# Sheet.net
KiCad netlist of a schematic drawn in Altium Designer
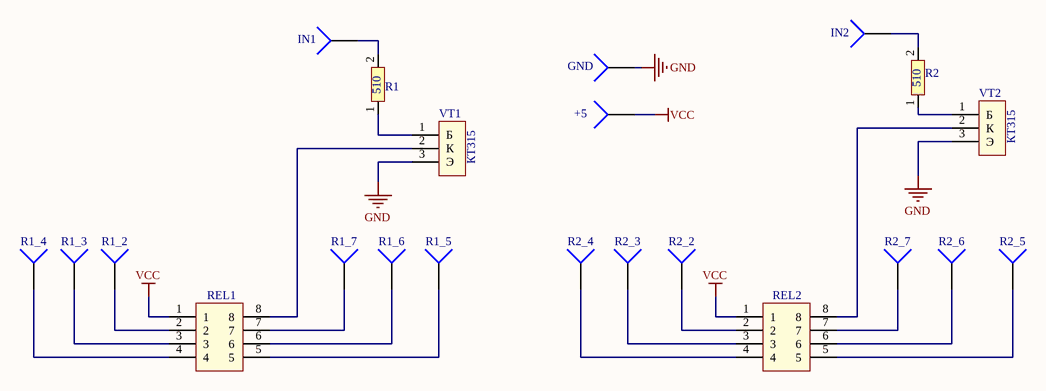
[diagram p0: Sheet.SchDoc]

(export (version "E")
  (design (tool "Eeschema 10.0.6"))
  (components
    (comp (ref "J1")
      (value "IN2")
      (footprint "PIN1")
      (description "Socket")
      (fields (field (name "PUBLISHER") "Altium Limited"))
      (libsource (lib "Miscellaneous Connectors") (part "Socket"))
    )
    (comp (ref "J2")
      (value "IN1")
      (footprint "PIN1")
      (description "Socket")
      (fields (field (name "PUBLISHER") "Altium Limited"))
      (libsource (lib "Miscellaneous Connectors") (part "Socket"))
    )
    (comp (ref "J3")
      (value "GND")
      (footprint "PIN1")
      (description "Socket")
      (fields (field (name "PUBLISHER") "Altium Limited"))
      (libsource (lib "Miscellaneous Connectors") (part "Socket"))
    )
    (comp (ref "J4")
      (value "+5")
      (footprint "PIN1")
      (description "Socket")
      (fields (field (name "PUBLISHER") "Altium Limited"))
      (libsource (lib "Miscellaneous Connectors") (part "Socket"))
    )
    (comp (ref "J5")
      (value "R1_4")
      (footprint "PIN1")
      (description "Socket")
      (fields (field (name "PUBLISHER") "Altium Limited"))
      (libsource (lib "Miscellaneous Connectors") (part "Socket"))
    )
    (comp (ref "J6")
      (value "R1_3")
      (footprint "PIN1")
      (description "Socket")
      (fields (field (name "PUBLISHER") "Altium Limited"))
      (libsource (lib "Miscellaneous Connectors") (part "Socket"))
    )
    (comp (ref "J7")
      (value "R1_2")
      (footprint "PIN1")
      (description "Socket")
      (fields (field (name "PUBLISHER") "Altium Limited"))
      (libsource (lib "Miscellaneous Connectors") (part "Socket"))
    )
    (comp (ref "J8")
      (value "R1_7")
      (footprint "PIN1")
      (description "Socket")
      (fields (field (name "PUBLISHER") "Altium Limited"))
      (libsource (lib "Miscellaneous Connectors") (part "Socket"))
    )
    (comp (ref "J9")
      (value "R1_6")
      (footprint "PIN1")
      (description "Socket")
      (fields (field (name "PUBLISHER") "Altium Limited"))
      (libsource (lib "Miscellaneous Connectors") (part "Socket"))
    )
    (comp (ref "J10")
      (value "R1_5")
      (footprint "PIN1")
      (description "Socket")
      (fields (field (name "PUBLISHER") "Altium Limited"))
      (libsource (lib "Miscellaneous Connectors") (part "Socket"))
    )
    (comp (ref "J11")
      (value "R2_4")
      (footprint "PIN1")
      (description "Socket")
      (fields (field (name "PUBLISHER") "Altium Limited"))
      (libsource (lib "Miscellaneous Connectors") (part "Socket"))
    )
    (comp (ref "J12")
      (value "R2_3")
      (footprint "PIN1")
      (description "Socket")
      (fields (field (name "PUBLISHER") "Altium Limited"))
      (libsource (lib "Miscellaneous Connectors") (part "Socket"))
    )
    (comp (ref "J13")
      (value "R2_2")
      (footprint "PIN1")
      (description "Socket")
      (fields (field (name "PUBLISHER") "Altium Limited"))
      (libsource (lib "Miscellaneous Connectors") (part "Socket"))
    )
    (comp (ref "J14")
      (value "R2_7")
      (footprint "PIN1")
      (description "Socket")
      (fields (field (name "PUBLISHER") "Altium Limited"))
      (libsource (lib "Miscellaneous Connectors") (part "Socket"))
    )
    (comp (ref "J15")
      (value "R2_6")
      (footprint "PIN1")
      (description "Socket")
      (fields (field (name "PUBLISHER") "Altium Limited"))
      (libsource (lib "Miscellaneous Connectors") (part "Socket"))
    )
    (comp (ref "J16")
      (value "R2_5")
      (footprint "PIN1")
      (description "Socket")
      (fields (field (name "PUBLISHER") "Altium Limited"))
      (libsource (lib "Miscellaneous Connectors") (part "Socket"))
    )
    (comp (ref "R1") (value "510") (footprint "RES") (libsource (lib "Schlib") (part "RES")))
    (comp (ref "R2") (value "510") (footprint "RES") (libsource (lib "Schlib") (part "RES")))
    (comp (ref "REL1") (value "IM03TS") (footprint "IM03TS") (libsource (lib "Schlib") (part "IM03TS")))
    (comp (ref "REL2") (value "IM03TS") (footprint "IM03TS") (libsource (lib "Schlib") (part "IM03TS")))
    (comp (ref "VT1") (value "КТ315") (footprint "KT315") (libsource (lib "Schlib") (part "КТ315")))
    (comp (ref "VT2") (value "КТ315") (footprint "KT315") (libsource (lib "Schlib") (part "КТ315")))
  )
  (nets
    (net (code "1") (name "GND") (class "Default")
      (node (ref "J3") (pin "1") (pinfunction "1_1") (pintype "passive"))
      (node (ref "VT1") (pin "3") (pinfunction "Э_3") (pintype "passive"))
      (node (ref "VT2") (pin "3") (pinfunction "Э_3") (pintype "passive"))
    )
    (net (code "2") (name "Net-(J1-Pad1)") (class "Default")
      (node (ref "J1") (pin "1") (pinfunction "1_1") (pintype "passive"))
      (node (ref "R2") (pin "2") (pinfunction "2_2") (pintype "passive"))
    )
    (net (code "3") (name "Net-(J2-Pad1)") (class "Default")
      (node (ref "J2") (pin "1") (pinfunction "1_1") (pintype "passive"))
      (node (ref "R1") (pin "2") (pinfunction "2_2") (pintype "passive"))
    )
    (net (code "4") (name "Net-(J5-Pad1)") (class "Default")
      (node (ref "J5") (pin "1") (pinfunction "1_1") (pintype "passive"))
      (node (ref "REL1") (pin "4") (pinfunction "4_4") (pintype "passive"))
    )
    (net (code "5") (name "Net-(J6-Pad1)") (class "Default")
      (node (ref "J6") (pin "1") (pinfunction "1_1") (pintype "passive"))
      (node (ref "REL1") (pin "3") (pinfunction "3_3") (pintype "passive"))
    )
    (net (code "6") (name "Net-(J7-Pad1)") (class "Default")
      (node (ref "J7") (pin "1") (pinfunction "1_1") (pintype "passive"))
      (node (ref "REL1") (pin "2") (pinfunction "2_2") (pintype "passive"))
    )
    (net (code "7") (name "Net-(J8-Pad1)") (class "Default")
      (node (ref "J8") (pin "1") (pinfunction "1_1") (pintype "passive"))
      (node (ref "REL1") (pin "7") (pinfunction "7_7") (pintype "passive"))
    )
    (net (code "8") (name "Net-(J9-Pad1)") (class "Default")
      (node (ref "J9") (pin "1") (pinfunction "1_1") (pintype "passive"))
      (node (ref "REL1") (pin "6") (pinfunction "6_6") (pintype "passive"))
    )
    (net (code "9") (name "Net-(J10-Pad1)") (class "Default")
      (node (ref "J10") (pin "1") (pinfunction "1_1") (pintype "passive"))
      (node (ref "REL1") (pin "5") (pinfunction "5_5") (pintype "passive"))
    )
    (net (code "10") (name "Net-(J11-Pad1)") (class "Default")
      (node (ref "J11") (pin "1") (pinfunction "1_1") (pintype "passive"))
      (node (ref "REL2") (pin "4") (pinfunction "4_4") (pintype "passive"))
    )
    (net (code "11") (name "Net-(J12-Pad1)") (class "Default")
      (node (ref "J12") (pin "1") (pinfunction "1_1") (pintype "passive"))
      (node (ref "REL2") (pin "3") (pinfunction "3_3") (pintype "passive"))
    )
    (net (code "12") (name "Net-(J13-Pad1)") (class "Default")
      (node (ref "J13") (pin "1") (pinfunction "1_1") (pintype "passive"))
      (node (ref "REL2") (pin "2") (pinfunction "2_2") (pintype "passive"))
    )
    (net (code "13") (name "Net-(J14-Pad1)") (class "Default")
      (node (ref "J14") (pin "1") (pinfunction "1_1") (pintype "passive"))
      (node (ref "REL2") (pin "7") (pinfunction "7_7") (pintype "passive"))
    )
    (net (code "14") (name "Net-(J15-Pad1)") (class "Default")
      (node (ref "J15") (pin "1") (pinfunction "1_1") (pintype "passive"))
      (node (ref "REL2") (pin "6") (pinfunction "6_6") (pintype "passive"))
    )
    (net (code "15") (name "Net-(J16-Pad1)") (class "Default")
      (node (ref "J16") (pin "1") (pinfunction "1_1") (pintype "passive"))
      (node (ref "REL2") (pin "5") (pinfunction "5_5") (pintype "passive"))
    )
    (net (code "16") (name "Net-(VT1-Б)") (class "Default")
      (node (ref "R1") (pin "1") (pinfunction "1_1") (pintype "passive"))
      (node (ref "VT1") (pin "1") (pinfunction "Б_1") (pintype "passive"))
    )
    (net (code "17") (name "Net-(VT1-К)") (class "Default")
      (node (ref "REL1") (pin "8") (pinfunction "8_8") (pintype "passive"))
      (node (ref "VT1") (pin "2") (pinfunction "К_2") (pintype "passive"))
    )
    (net (code "18") (name "Net-(VT2-Б)") (class "Default")
      (node (ref "R2") (pin "1") (pinfunction "1_1") (pintype "passive"))
      (node (ref "VT2") (pin "1") (pinfunction "Б_1") (pintype "passive"))
    )
    (net (code "19") (name "Net-(VT2-К)") (class "Default")
      (node (ref "REL2") (pin "8") (pinfunction "8_8") (pintype "passive"))
      (node (ref "VT2") (pin "2") (pinfunction "К_2") (pintype "passive"))
    )
    (net (code "20") (name "VCC") (class "Default")
      (node (ref "J4") (pin "1") (pinfunction "1_1") (pintype "passive"))
      (node (ref "REL1") (pin "1") (pinfunction "1_1") (pintype "passive"))
      (node (ref "REL2") (pin "1") (pinfunction "1_1") (pintype "passive"))
    )
  )
)
